# receiver_2.net
KiCad netlist of a schematic drawn in Altium Designer
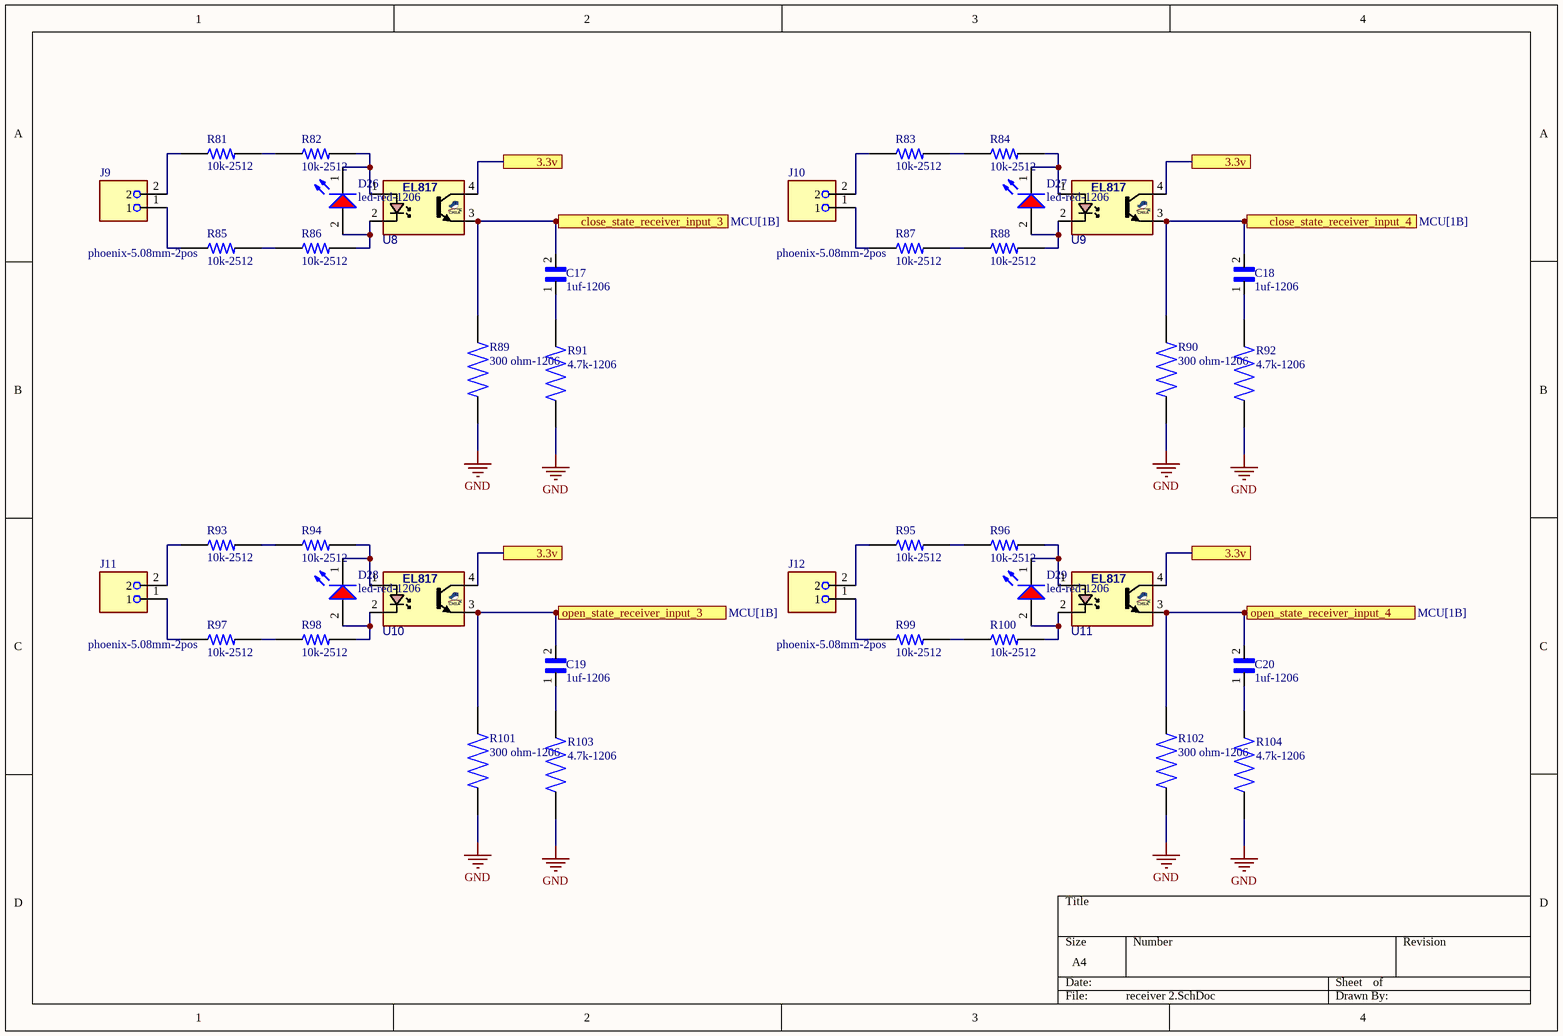
[diagram p0: receiver 2.SchDoc]

(export (version "E")
  (design (tool "Eeschema 10.0.6"))
  (components
    (comp (ref "C17")
      (value "1uf-1206")
      (footprint "CAPC3216X180N")
      (description "1ÂµF Â±20% 50V Ceramic Capacitor X8R 1206 (3216 Metric)")
      (fields (field (name "MF") "TDK") (field (name "MP") "CGA5L3X8R1H105M160AB"))
      (libsource (lib "cap-1206") (part "CGA5L3X8R1H105M160AB"))
    )
    (comp (ref "C18")
      (value "1uf-1206")
      (footprint "CAPC3216X180N")
      (description "1ÂµF Â±20% 50V Ceramic Capacitor X8R 1206 (3216 Metric)")
      (fields (field (name "MF") "TDK") (field (name "MP") "CGA5L3X8R1H105M160AB"))
      (libsource (lib "cap-1206") (part "CGA5L3X8R1H105M160AB"))
    )
    (comp (ref "C19")
      (value "1uf-1206")
      (footprint "CAPC3216X180N")
      (description "1ÂµF Â±20% 50V Ceramic Capacitor X8R 1206 (3216 Metric)")
      (fields (field (name "MF") "TDK") (field (name "MP") "CGA5L3X8R1H105M160AB"))
      (libsource (lib "cap-1206") (part "CGA5L3X8R1H105M160AB"))
    )
    (comp (ref "C20")
      (value "1uf-1206")
      (footprint "CAPC3216X180N")
      (description "1ÂµF Â±20% 50V Ceramic Capacitor X8R 1206 (3216 Metric)")
      (fields (field (name "MF") "TDK") (field (name "MP") "CGA5L3X8R1H105M160AB"))
      (libsource (lib "cap-1206") (part "CGA5L3X8R1H105M160AB"))
    )
    (comp (ref "D26")
      (value "led-red-1206")
      (footprint "WL-SMRW_1206 dome_normal use")
      (description "WL-SMRW Mono-color Reverse mount Waterclear, SMT, size 1206 dome, Red, 2V, 20°")
      (fields
        (field (name "MANUFACTURER PART NUMBER") "156120RS82500")
        (field (name "MANUFACTURER") "Wurth Elektronik")
      )
      (libsource (lib "led-1206") (part "156120RS82500"))
    )
    (comp (ref "D27")
      (value "led-red-1206")
      (footprint "WL-SMRW_1206 dome_normal use")
      (description "WL-SMRW Mono-color Reverse mount Waterclear, SMT, size 1206 dome, Red, 2V, 20°")
      (fields
        (field (name "MANUFACTURER PART NUMBER") "156120RS82500")
        (field (name "MANUFACTURER") "Wurth Elektronik")
      )
      (libsource (lib "led-1206") (part "156120RS82500"))
    )
    (comp (ref "D28")
      (value "led-red-1206")
      (footprint "WL-SMRW_1206 dome_normal use")
      (description "WL-SMRW Mono-color Reverse mount Waterclear, SMT, size 1206 dome, Red, 2V, 20°")
      (fields
        (field (name "MANUFACTURER PART NUMBER") "156120RS82500")
        (field (name "MANUFACTURER") "Wurth Elektronik")
      )
      (libsource (lib "led-1206") (part "156120RS82500"))
    )
    (comp (ref "D29")
      (value "led-red-1206")
      (footprint "WL-SMRW_1206 dome_normal use")
      (description "WL-SMRW Mono-color Reverse mount Waterclear, SMT, size 1206 dome, Red, 2V, 20°")
      (fields
        (field (name "MANUFACTURER PART NUMBER") "156120RS82500")
        (field (name "MANUFACTURER") "Wurth Elektronik")
      )
      (libsource (lib "led-1206") (part "156120RS82500"))
    )
    (comp (ref "J9")
      (value "phoenix-5.08mm-2pos")
      (footprint "PHOENIX_1715721")
      (fields (field (name "MP") "1715721"))
      (libsource (lib "phoenix-2pos") (part "1715721"))
    )
    (comp (ref "J10")
      (value "phoenix-5.08mm-2pos")
      (footprint "PHOENIX_1715721")
      (fields (field (name "MP") "1715721"))
      (libsource (lib "phoenix-2pos") (part "1715721"))
    )
    (comp (ref "J11")
      (value "phoenix-5.08mm-2pos")
      (footprint "PHOENIX_1715721")
      (fields (field (name "MP") "1715721"))
      (libsource (lib "phoenix-2pos") (part "1715721"))
    )
    (comp (ref "J12")
      (value "phoenix-5.08mm-2pos")
      (footprint "PHOENIX_1715721")
      (fields (field (name "MP") "1715721"))
      (libsource (lib "phoenix-2pos") (part "1715721"))
    )
    (comp (ref "R81")
      (value "10k-2512")
      (footprint "RESC6331X70N")
      (description "18 kOhms Â±5% 1.5W Chip Resistor 2512 (6432 Metric) Pulse Withstanding Thick Film")
      (fields (field (name "MF") "TE Connectivity") (field (name "MP") "5-2176246-2"))
      (libsource (lib "resistor-2512") (part "5-2176246-2"))
    )
    (comp (ref "R82")
      (value "10k-2512")
      (footprint "RESC6331X70N")
      (description "18 kOhms Â±5% 1.5W Chip Resistor 2512 (6432 Metric) Pulse Withstanding Thick Film")
      (fields (field (name "MF") "TE Connectivity") (field (name "MP") "5-2176246-2"))
      (libsource (lib "resistor-2512") (part "5-2176246-2"))
    )
    (comp (ref "R83")
      (value "10k-2512")
      (footprint "RESC6331X70N")
      (description "18 kOhms Â±5% 1.5W Chip Resistor 2512 (6432 Metric) Pulse Withstanding Thick Film")
      (fields (field (name "MF") "TE Connectivity") (field (name "MP") "5-2176246-2"))
      (libsource (lib "resistor-2512") (part "5-2176246-2"))
    )
    (comp (ref "R84")
      (value "10k-2512")
      (footprint "RESC6331X70N")
      (description "18 kOhms Â±5% 1.5W Chip Resistor 2512 (6432 Metric) Pulse Withstanding Thick Film")
      (fields (field (name "MF") "TE Connectivity") (field (name "MP") "5-2176246-2"))
      (libsource (lib "resistor-2512") (part "5-2176246-2"))
    )
    (comp (ref "R85")
      (value "10k-2512")
      (footprint "RESC6331X70N")
      (description "18 kOhms Â±5% 1.5W Chip Resistor 2512 (6432 Metric) Pulse Withstanding Thick Film")
      (fields (field (name "MF") "TE Connectivity") (field (name "MP") "5-2176246-2"))
      (libsource (lib "resistor-2512") (part "5-2176246-2"))
    )
    (comp (ref "R86")
      (value "10k-2512")
      (footprint "RESC6331X70N")
      (description "18 kOhms Â±5% 1.5W Chip Resistor 2512 (6432 Metric) Pulse Withstanding Thick Film")
      (fields (field (name "MF") "TE Connectivity") (field (name "MP") "5-2176246-2"))
      (libsource (lib "resistor-2512") (part "5-2176246-2"))
    )
    (comp (ref "R87")
      (value "10k-2512")
      (footprint "RESC6331X70N")
      (description "18 kOhms Â±5% 1.5W Chip Resistor 2512 (6432 Metric) Pulse Withstanding Thick Film")
      (fields (field (name "MF") "TE Connectivity") (field (name "MP") "5-2176246-2"))
      (libsource (lib "resistor-2512") (part "5-2176246-2"))
    )
    (comp (ref "R88")
      (value "10k-2512")
      (footprint "RESC6331X70N")
      (description "18 kOhms Â±5% 1.5W Chip Resistor 2512 (6432 Metric) Pulse Withstanding Thick Film")
      (fields (field (name "MF") "TE Connectivity") (field (name "MP") "5-2176246-2"))
      (libsource (lib "resistor-2512") (part "5-2176246-2"))
    )
    (comp (ref "R89")
      (value "300 ohm-1206")
      (footprint "RESC3015X65N")
      (description "Res Thin Film 1206 10K Ohm 0.1% 1/8W Â±25ppm/Â°C Molded SMD SMD Paper T/R")
      (fields (field (name "MF") "TE Connectivity") (field (name "MP") "CPF1206B10KE1"))
      (libsource (lib "resistor-1206") (part "CPF1206B10KE1"))
    )
    (comp (ref "R90")
      (value "300 ohm-1206")
      (footprint "RESC3015X65N")
      (description "Res Thin Film 1206 10K Ohm 0.1% 1/8W Â±25ppm/Â°C Molded SMD SMD Paper T/R")
      (fields (field (name "MF") "TE Connectivity") (field (name "MP") "CPF1206B10KE1"))
      (libsource (lib "resistor-1206") (part "CPF1206B10KE1"))
    )
    (comp (ref "R91")
      (value "4.7k-1206")
      (footprint "RESC3015X65N")
      (description "Res Thin Film 1206 10K Ohm 0.1% 1/8W Â±25ppm/Â°C Molded SMD SMD Paper T/R")
      (fields (field (name "MF") "TE Connectivity") (field (name "MP") "CPF1206B10KE1"))
      (libsource (lib "resistor-1206") (part "CPF1206B10KE1"))
    )
    (comp (ref "R92")
      (value "4.7k-1206")
      (footprint "RESC3015X65N")
      (description "Res Thin Film 1206 10K Ohm 0.1% 1/8W Â±25ppm/Â°C Molded SMD SMD Paper T/R")
      (fields (field (name "MF") "TE Connectivity") (field (name "MP") "CPF1206B10KE1"))
      (libsource (lib "resistor-1206") (part "CPF1206B10KE1"))
    )
    (comp (ref "R93")
      (value "10k-2512")
      (footprint "RESC6331X70N")
      (description "18 kOhms Â±5% 1.5W Chip Resistor 2512 (6432 Metric) Pulse Withstanding Thick Film")
      (fields (field (name "MF") "TE Connectivity") (field (name "MP") "5-2176246-2"))
      (libsource (lib "resistor-2512") (part "5-2176246-2"))
    )
    (comp (ref "R94")
      (value "10k-2512")
      (footprint "RESC6331X70N")
      (description "18 kOhms Â±5% 1.5W Chip Resistor 2512 (6432 Metric) Pulse Withstanding Thick Film")
      (fields (field (name "MF") "TE Connectivity") (field (name "MP") "5-2176246-2"))
      (libsource (lib "resistor-2512") (part "5-2176246-2"))
    )
    (comp (ref "R95")
      (value "10k-2512")
      (footprint "RESC6331X70N")
      (description "18 kOhms Â±5% 1.5W Chip Resistor 2512 (6432 Metric) Pulse Withstanding Thick Film")
      (fields (field (name "MF") "TE Connectivity") (field (name "MP") "5-2176246-2"))
      (libsource (lib "resistor-2512") (part "5-2176246-2"))
    )
    (comp (ref "R96")
      (value "10k-2512")
      (footprint "RESC6331X70N")
      (description "18 kOhms Â±5% 1.5W Chip Resistor 2512 (6432 Metric) Pulse Withstanding Thick Film")
      (fields (field (name "MF") "TE Connectivity") (field (name "MP") "5-2176246-2"))
      (libsource (lib "resistor-2512") (part "5-2176246-2"))
    )
    (comp (ref "R97")
      (value "10k-2512")
      (footprint "RESC6331X70N")
      (description "18 kOhms Â±5% 1.5W Chip Resistor 2512 (6432 Metric) Pulse Withstanding Thick Film")
      (fields (field (name "MF") "TE Connectivity") (field (name "MP") "5-2176246-2"))
      (libsource (lib "resistor-2512") (part "5-2176246-2"))
    )
    (comp (ref "R98")
      (value "10k-2512")
      (footprint "RESC6331X70N")
      (description "18 kOhms Â±5% 1.5W Chip Resistor 2512 (6432 Metric) Pulse Withstanding Thick Film")
      (fields (field (name "MF") "TE Connectivity") (field (name "MP") "5-2176246-2"))
      (libsource (lib "resistor-2512") (part "5-2176246-2"))
    )
    (comp (ref "R99")
      (value "10k-2512")
      (footprint "RESC6331X70N")
      (description "18 kOhms Â±5% 1.5W Chip Resistor 2512 (6432 Metric) Pulse Withstanding Thick Film")
      (fields (field (name "MF") "TE Connectivity") (field (name "MP") "5-2176246-2"))
      (libsource (lib "resistor-2512") (part "5-2176246-2"))
    )
    (comp (ref "R100")
      (value "10k-2512")
      (footprint "RESC6331X70N")
      (description "18 kOhms Â±5% 1.5W Chip Resistor 2512 (6432 Metric) Pulse Withstanding Thick Film")
      (fields (field (name "MF") "TE Connectivity") (field (name "MP") "5-2176246-2"))
      (libsource (lib "resistor-2512") (part "5-2176246-2"))
    )
    (comp (ref "R101")
      (value "300 ohm-1206")
      (footprint "RESC3015X65N")
      (description "Res Thin Film 1206 10K Ohm 0.1% 1/8W Â±25ppm/Â°C Molded SMD SMD Paper T/R")
      (fields (field (name "MF") "TE Connectivity") (field (name "MP") "CPF1206B10KE1"))
      (libsource (lib "resistor-1206") (part "CPF1206B10KE1"))
    )
    (comp (ref "R102")
      (value "300 ohm-1206")
      (footprint "RESC3015X65N")
      (description "Res Thin Film 1206 10K Ohm 0.1% 1/8W Â±25ppm/Â°C Molded SMD SMD Paper T/R")
      (fields (field (name "MF") "TE Connectivity") (field (name "MP") "CPF1206B10KE1"))
      (libsource (lib "resistor-1206") (part "CPF1206B10KE1"))
    )
    (comp (ref "R103")
      (value "4.7k-1206")
      (footprint "RESC3015X65N")
      (description "Res Thin Film 1206 10K Ohm 0.1% 1/8W Â±25ppm/Â°C Molded SMD SMD Paper T/R")
      (fields (field (name "MF") "TE Connectivity") (field (name "MP") "CPF1206B10KE1"))
      (libsource (lib "resistor-1206") (part "CPF1206B10KE1"))
    )
    (comp (ref "R104")
      (value "4.7k-1206")
      (footprint "RESC3015X65N")
      (description "Res Thin Film 1206 10K Ohm 0.1% 1/8W Â±25ppm/Â°C Molded SMD SMD Paper T/R")
      (fields (field (name "MF") "TE Connectivity") (field (name "MP") "CPF1206B10KE1"))
      (libsource (lib "resistor-1206") (part "CPF1206B10KE1"))
    )
    (comp (ref "U8")
      (value "EL817")
      (footprint "DIP_4SMD")
      (description "OPTOCOUPLER, TRANSISTOR, 4PIN")
      (libsource (lib "optocoupler") (part "OPTC_TR4P_EL817_SMD"))
    )
    (comp (ref "U9")
      (value "EL817")
      (footprint "DIP_4SMD")
      (description "OPTOCOUPLER, TRANSISTOR, 4PIN")
      (libsource (lib "optocoupler") (part "OPTC_TR4P_EL817_SMD"))
    )
    (comp (ref "U10")
      (value "EL817")
      (footprint "DIP_4SMD")
      (description "OPTOCOUPLER, TRANSISTOR, 4PIN")
      (libsource (lib "optocoupler") (part "OPTC_TR4P_EL817_SMD"))
    )
    (comp (ref "U11")
      (value "EL817")
      (footprint "DIP_4SMD")
      (description "OPTOCOUPLER, TRANSISTOR, 4PIN")
      (libsource (lib "optocoupler") (part "OPTC_TR4P_EL817_SMD"))
    )
  )
  (nets
    (net (code "1") (name "/3.3v") (class "Default")
      (node (ref "U10") (pin "4") (pinfunction "C_4") (pintype "passive"))
      (node (ref "U11") (pin "4") (pinfunction "C_4") (pintype "passive"))
      (node (ref "U8") (pin "4") (pinfunction "C_4") (pintype "passive"))
      (node (ref "U9") (pin "4") (pinfunction "C_4") (pintype "passive"))
    )
    (net (code "2") (name "/close_state_receiver_input_3") (class "Default")
      (node (ref "C17") (pin "2") (pinfunction "2_2") (pintype "passive"))
      (node (ref "R89") (pin "2") (pinfunction "2_2") (pintype "passive"))
      (node (ref "U8") (pin "3") (pinfunction "E_3") (pintype "passive"))
    )
    (net (code "3") (name "/close_state_receiver_input_4") (class "Default")
      (node (ref "C18") (pin "2") (pinfunction "2_2") (pintype "passive"))
      (node (ref "R90") (pin "2") (pinfunction "2_2") (pintype "passive"))
      (node (ref "U9") (pin "3") (pinfunction "E_3") (pintype "passive"))
    )
    (net (code "4") (name "/open_state_receiver_input_3") (class "Default")
      (node (ref "C19") (pin "2") (pinfunction "2_2") (pintype "passive"))
      (node (ref "R101") (pin "2") (pinfunction "2_2") (pintype "passive"))
      (node (ref "U10") (pin "3") (pinfunction "E_3") (pintype "passive"))
    )
    (net (code "5") (name "/open_state_receiver_input_4") (class "Default")
      (node (ref "C20") (pin "2") (pinfunction "2_2") (pintype "passive"))
      (node (ref "R102") (pin "2") (pinfunction "2_2") (pintype "passive"))
      (node (ref "U11") (pin "3") (pinfunction "E_3") (pintype "passive"))
    )
    (net (code "6") (name "GND") (class "Default")
      (node (ref "R101") (pin "1") (pinfunction "1_1") (pintype "passive"))
      (node (ref "R102") (pin "1") (pinfunction "1_1") (pintype "passive"))
      (node (ref "R103") (pin "1") (pinfunction "1_1") (pintype "passive"))
      (node (ref "R104") (pin "1") (pinfunction "1_1") (pintype "passive"))
      (node (ref "R89") (pin "1") (pinfunction "1_1") (pintype "passive"))
      (node (ref "R90") (pin "1") (pinfunction "1_1") (pintype "passive"))
      (node (ref "R91") (pin "1") (pinfunction "1_1") (pintype "passive"))
      (node (ref "R92") (pin "1") (pinfunction "1_1") (pintype "passive"))
    )
    (net (code "7") (name "Net-(C17-Pad1)") (class "Default")
      (node (ref "C17") (pin "1") (pinfunction "1_1") (pintype "passive"))
      (node (ref "R91") (pin "2") (pinfunction "2_2") (pintype "passive"))
    )
    (net (code "8") (name "Net-(C18-Pad1)") (class "Default")
      (node (ref "C18") (pin "1") (pinfunction "1_1") (pintype "passive"))
      (node (ref "R92") (pin "2") (pinfunction "2_2") (pintype "passive"))
    )
    (net (code "9") (name "Net-(C19-Pad1)") (class "Default")
      (node (ref "C19") (pin "1") (pinfunction "1_1") (pintype "passive"))
      (node (ref "R103") (pin "2") (pinfunction "2_2") (pintype "passive"))
    )
    (net (code "10") (name "Net-(C20-Pad1)") (class "Default")
      (node (ref "C20") (pin "1") (pinfunction "1_1") (pintype "passive"))
      (node (ref "R104") (pin "2") (pinfunction "2_2") (pintype "passive"))
    )
    (net (code "11") (name "Net-(D26-A)") (class "Default")
      (node (ref "D26") (pin "2") (pinfunction "A_2") (pintype "passive"))
      (node (ref "R86") (pin "2") (pinfunction "2_2") (pintype "passive"))
      (node (ref "U8") (pin "2") (pinfunction "K_2") (pintype "passive"))
    )
    (net (code "12") (name "Net-(D26-K)") (class "Default")
      (node (ref "D26") (pin "1") (pinfunction "K_1") (pintype "passive"))
      (node (ref "R82") (pin "2") (pinfunction "2_2") (pintype "passive"))
      (node (ref "U8") (pin "1") (pinfunction "A_1") (pintype "passive"))
    )
    (net (code "13") (name "Net-(D27-A)") (class "Default")
      (node (ref "D27") (pin "2") (pinfunction "A_2") (pintype "passive"))
      (node (ref "R88") (pin "2") (pinfunction "2_2") (pintype "passive"))
      (node (ref "U9") (pin "2") (pinfunction "K_2") (pintype "passive"))
    )
    (net (code "14") (name "Net-(D27-K)") (class "Default")
      (node (ref "D27") (pin "1") (pinfunction "K_1") (pintype "passive"))
      (node (ref "R84") (pin "2") (pinfunction "2_2") (pintype "passive"))
      (node (ref "U9") (pin "1") (pinfunction "A_1") (pintype "passive"))
    )
    (net (code "15") (name "Net-(D28-A)") (class "Default")
      (node (ref "D28") (pin "2") (pinfunction "A_2") (pintype "passive"))
      (node (ref "R98") (pin "2") (pinfunction "2_2") (pintype "passive"))
      (node (ref "U10") (pin "2") (pinfunction "K_2") (pintype "passive"))
    )
    (net (code "16") (name "Net-(D28-K)") (class "Default")
      (node (ref "D28") (pin "1") (pinfunction "K_1") (pintype "passive"))
      (node (ref "R94") (pin "2") (pinfunction "2_2") (pintype "passive"))
      (node (ref "U10") (pin "1") (pinfunction "A_1") (pintype "passive"))
    )
    (net (code "17") (name "Net-(D29-A)") (class "Default")
      (node (ref "D29") (pin "2") (pinfunction "A_2") (pintype "passive"))
      (node (ref "R100") (pin "2") (pinfunction "2_2") (pintype "passive"))
      (node (ref "U11") (pin "2") (pinfunction "K_2") (pintype "passive"))
    )
    (net (code "18") (name "Net-(D29-K)") (class "Default")
      (node (ref "D29") (pin "1") (pinfunction "K_1") (pintype "passive"))
      (node (ref "R96") (pin "2") (pinfunction "2_2") (pintype "passive"))
      (node (ref "U11") (pin "1") (pinfunction "A_1") (pintype "passive"))
    )
    (net (code "19") (name "Net-(J9-Pad1)") (class "Default")
      (node (ref "J9") (pin "1") (pinfunction "1_1") (pintype "passive"))
      (node (ref "R85") (pin "1") (pinfunction "1_1") (pintype "passive"))
    )
    (net (code "20") (name "Net-(J9-Pad2)") (class "Default")
      (node (ref "J9") (pin "2") (pinfunction "2_2") (pintype "passive"))
      (node (ref "R81") (pin "1") (pinfunction "1_1") (pintype "passive"))
    )
    (net (code "21") (name "Net-(J10-Pad1)") (class "Default")
      (node (ref "J10") (pin "1") (pinfunction "1_1") (pintype "passive"))
      (node (ref "R87") (pin "1") (pinfunction "1_1") (pintype "passive"))
    )
    (net (code "22") (name "Net-(J10-Pad2)") (class "Default")
      (node (ref "J10") (pin "2") (pinfunction "2_2") (pintype "passive"))
      (node (ref "R83") (pin "1") (pinfunction "1_1") (pintype "passive"))
    )
    (net (code "23") (name "Net-(J11-Pad1)") (class "Default")
      (node (ref "J11") (pin "1") (pinfunction "1_1") (pintype "passive"))
      (node (ref "R97") (pin "1") (pinfunction "1_1") (pintype "passive"))
    )
    (net (code "24") (name "Net-(J11-Pad2)") (class "Default")
      (node (ref "J11") (pin "2") (pinfunction "2_2") (pintype "passive"))
      (node (ref "R93") (pin "1") (pinfunction "1_1") (pintype "passive"))
    )
    (net (code "25") (name "Net-(J12-Pad1)") (class "Default")
      (node (ref "J12") (pin "1") (pinfunction "1_1") (pintype "passive"))
      (node (ref "R99") (pin "1") (pinfunction "1_1") (pintype "passive"))
    )
    (net (code "26") (name "Net-(J12-Pad2)") (class "Default")
      (node (ref "J12") (pin "2") (pinfunction "2_2") (pintype "passive"))
      (node (ref "R95") (pin "1") (pinfunction "1_1") (pintype "passive"))
    )
    (net (code "27") (name "Net-(R81-Pad2)") (class "Default")
      (node (ref "R81") (pin "2") (pinfunction "2_2") (pintype "passive"))
      (node (ref "R82") (pin "1") (pinfunction "1_1") (pintype "passive"))
    )
    (net (code "28") (name "Net-(R83-Pad2)") (class "Default")
      (node (ref "R83") (pin "2") (pinfunction "2_2") (pintype "passive"))
      (node (ref "R84") (pin "1") (pinfunction "1_1") (pintype "passive"))
    )
    (net (code "29") (name "Net-(R85-Pad2)") (class "Default")
      (node (ref "R85") (pin "2") (pinfunction "2_2") (pintype "passive"))
      (node (ref "R86") (pin "1") (pinfunction "1_1") (pintype "passive"))
    )
    (net (code "30") (name "Net-(R87-Pad2)") (class "Default")
      (node (ref "R87") (pin "2") (pinfunction "2_2") (pintype "passive"))
      (node (ref "R88") (pin "1") (pinfunction "1_1") (pintype "passive"))
    )
    (net (code "31") (name "Net-(R93-Pad2)") (class "Default")
      (node (ref "R93") (pin "2") (pinfunction "2_2") (pintype "passive"))
      (node (ref "R94") (pin "1") (pinfunction "1_1") (pintype "passive"))
    )
    (net (code "32") (name "Net-(R95-Pad2)") (class "Default")
      (node (ref "R95") (pin "2") (pinfunction "2_2") (pintype "passive"))
      (node (ref "R96") (pin "1") (pinfunction "1_1") (pintype "passive"))
    )
    (net (code "33") (name "Net-(R97-Pad2)") (class "Default")
      (node (ref "R97") (pin "2") (pinfunction "2_2") (pintype "passive"))
      (node (ref "R98") (pin "1") (pinfunction "1_1") (pintype "passive"))
    )
    (net (code "34") (name "Net-(R100-Pad1)") (class "Default")
      (node (ref "R100") (pin "1") (pinfunction "1_1") (pintype "passive"))
      (node (ref "R99") (pin "2") (pinfunction "2_2") (pintype "passive"))
    )
  )
)
